# 5V.net
KiCad netlist of a schematic drawn in Altium Designer
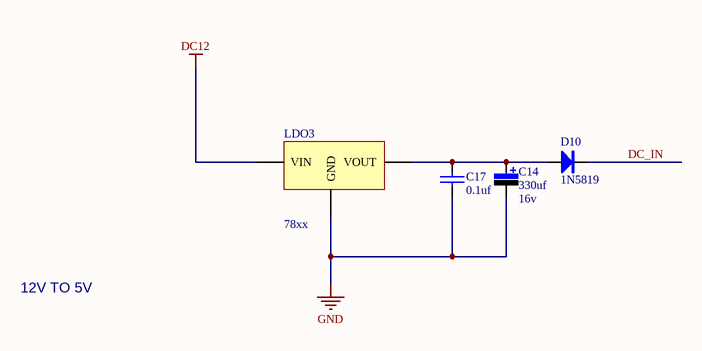
[diagram p0: 5V.SchDoc]

(export (version "E")
  (design (tool "Eeschema 10.0.6"))
  (components
    (comp (ref "C14")
      (value "16v")
      (footprint "CAP 16v330uf（6*8）")
      (description "电解电容")
      (fields (field (name "ALTIUM_VALUE") "330uf") (field (name "Comment") "05.Cap-EC"))
      (libsource (lib "电子元件") (part "05.Cap-EC"))
    )
    (comp (ref "C17")
      (value "0.1uf")
      (footprint "C 0603")
      (description "电容")
      (fields (field (name "Comment") "04.Cap"))
      (libsource (lib "电子元件") (part "04.Cap"))
    )
    (comp (ref "D10")
      (value "1N5819")
      (footprint "D 1N5819W-SOD123")
      (description "二极管")
      (libsource (lib "电子元件") (part "12.Diode"))
    )
    (comp (ref "LDO3")
      (value "78xx")
      (footprint "78M05")
      (description "线性稳压芯片")
      (fields (field (name "版权归属") "源创客"))
      (libsource (lib "集成IC") (part "78xx"))
    )
  )
  (nets
    (net (code "1") (name "/DC_IN") (class "Default")
      (node (ref "D10") (pin "K") (pinfunction "K_K") (pintype "passive"))
    )
    (net (code "2") (name "DC12") (class "Default")
      (node (ref "LDO3") (pin "VIN") (pinfunction "VIN_VIN") (pintype "passive"))
    )
    (net (code "3") (name "GND") (class "Default")
      (node (ref "C14") (pin "2") (pinfunction "2_2") (pintype "passive"))
      (node (ref "C17") (pin "2") (pinfunction "2_2") (pintype "passive"))
      (node (ref "LDO3") (pin "GND") (pinfunction "GND_GND") (pintype "passive"))
    )
    (net (code "4") (name "Net-(C14-Pad1)") (class "Default")
      (node (ref "C14") (pin "1") (pinfunction "1_1") (pintype "passive"))
      (node (ref "C17") (pin "1") (pinfunction "1_1") (pintype "passive"))
      (node (ref "D10") (pin "A") (pinfunction "A_A") (pintype "passive"))
      (node (ref "LDO3") (pin "VOUT") (pinfunction "VOUT_VOUT") (pintype "passive"))
    )
  )
)
